# bipop_power_supply.net
KiCad netlist of a schematic drawn in EAGLE
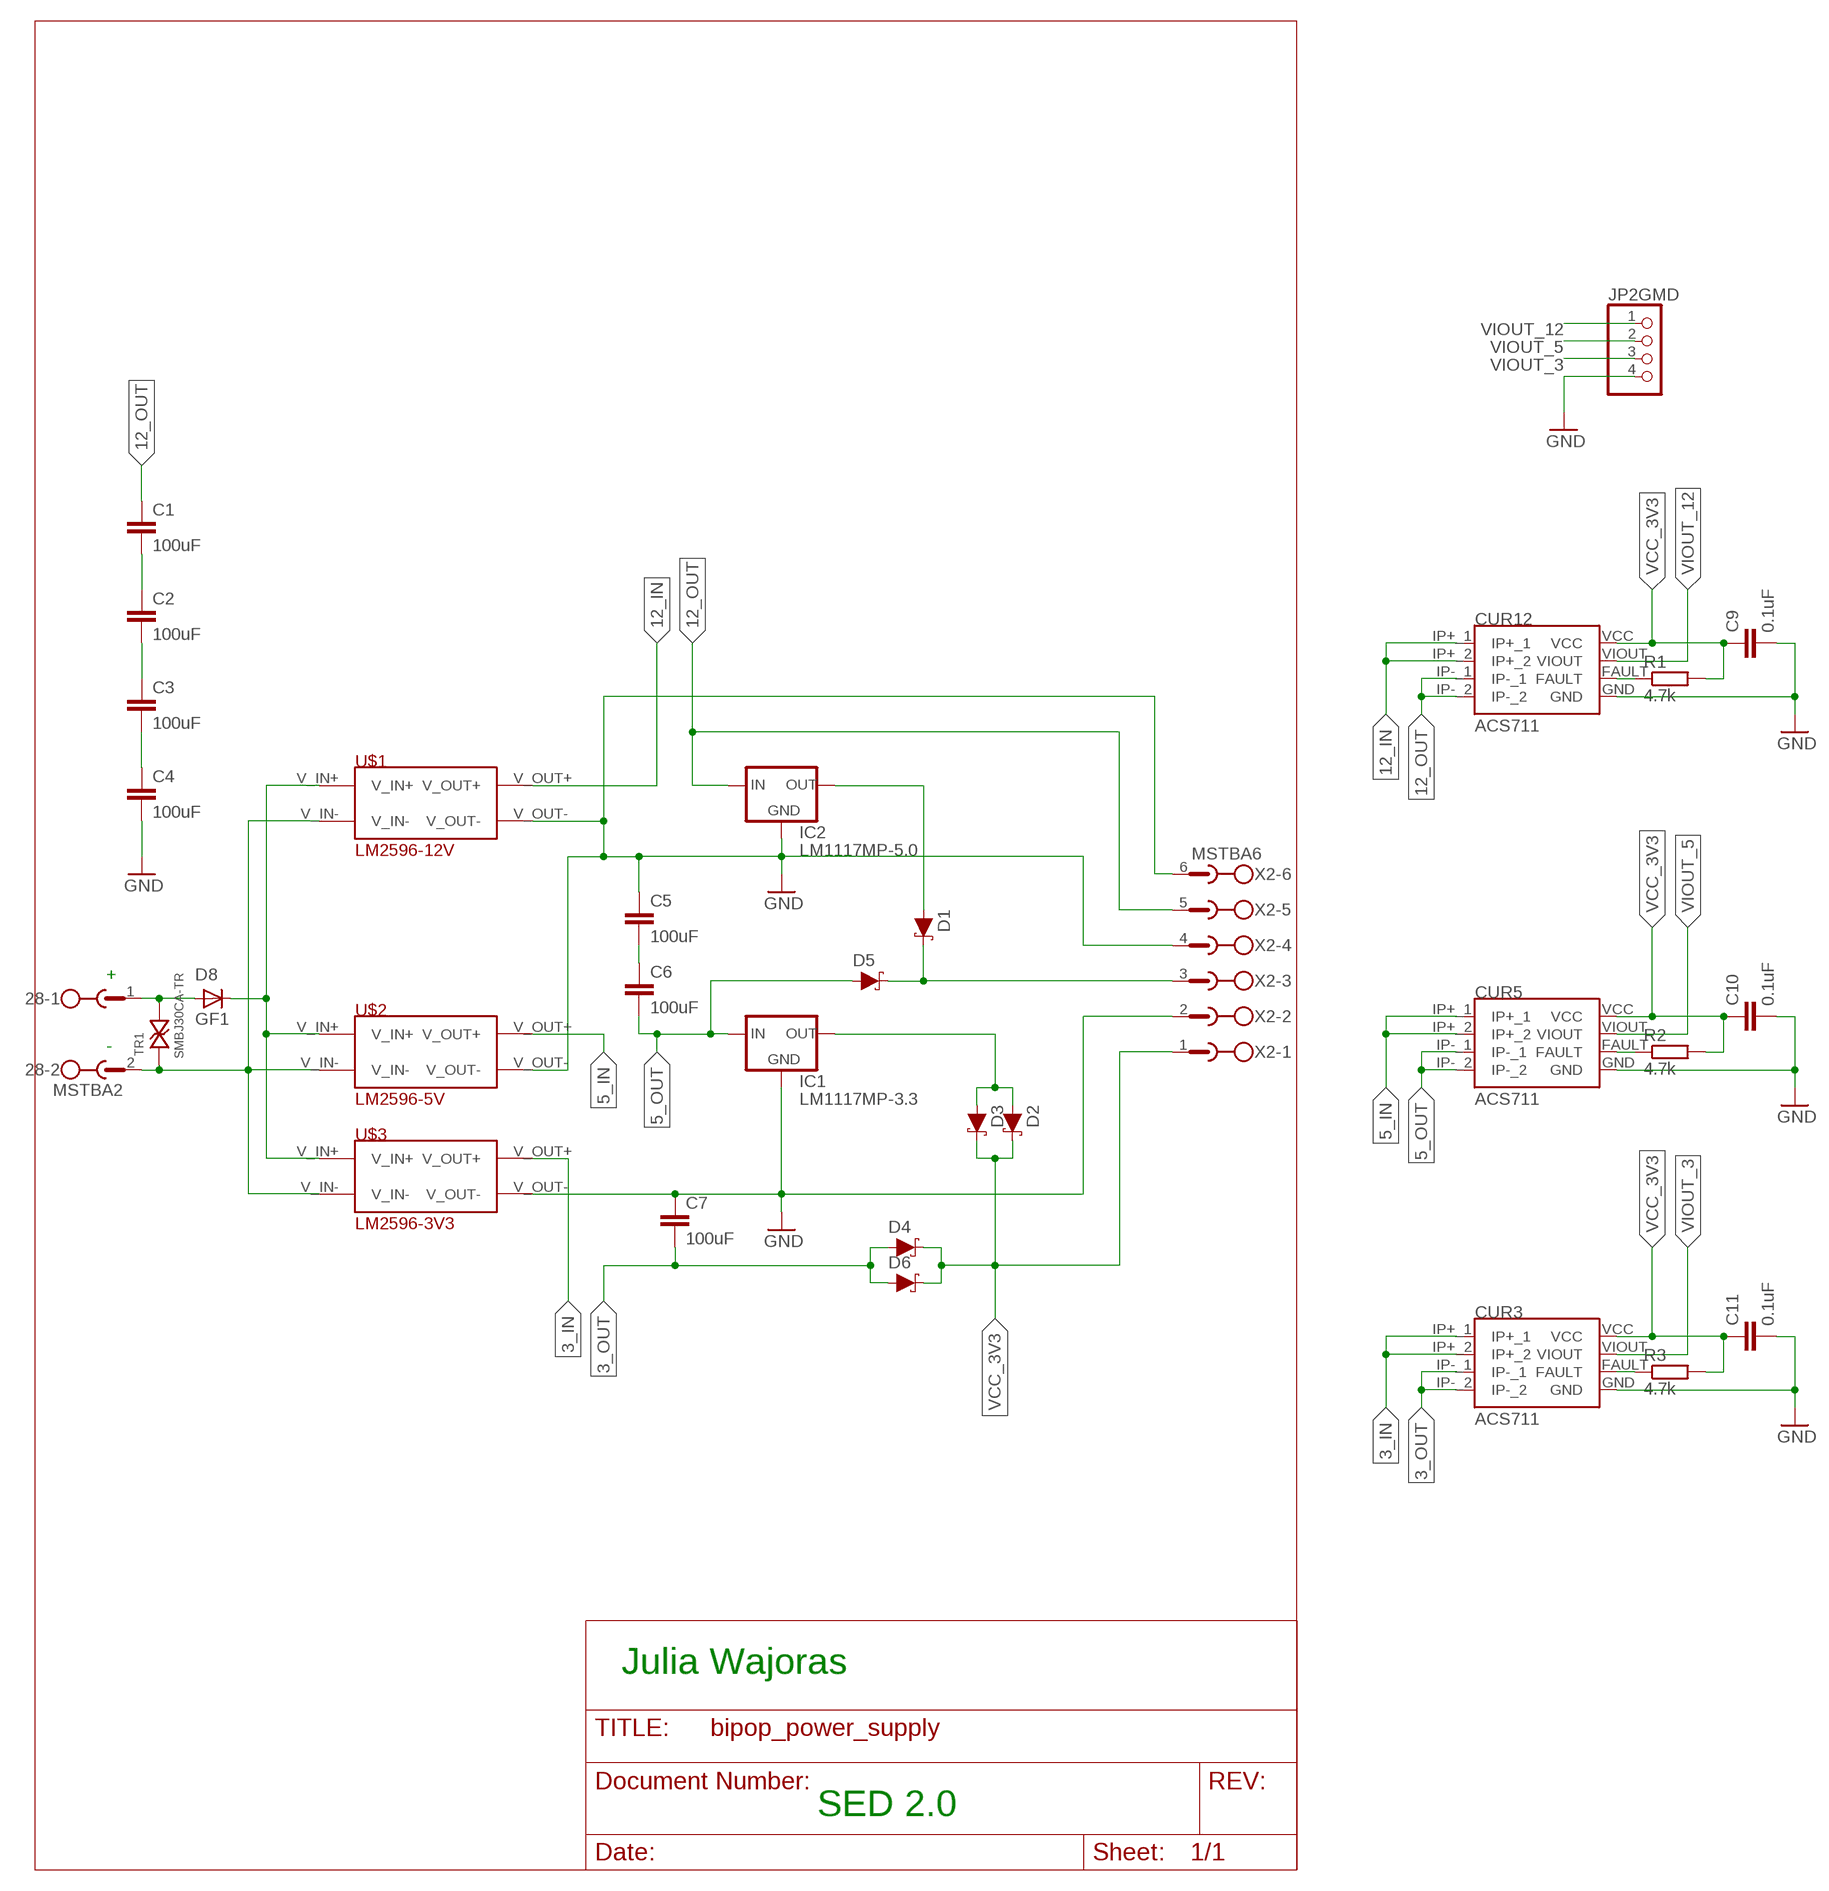
[diagram p0: schematic, sheet 1]

(export (version "E")
  (design (tool "Eeschema 10.0.6"))
  (components
    (comp (ref "28")
      (value "MSTBA2")
      (footprint "eagle-import:MSTBA2")
      (libsource (lib "eagle-import") (part "MSTBA2"))
    )
    (comp (ref "C1")
      (value "100uF")
      (footprint "eagle-import:C0805")
      (libsource (lib "eagle-import") (part "C-EUC0805"))
    )
    (comp (ref "C2")
      (value "100uF")
      (footprint "eagle-import:C0805")
      (libsource (lib "eagle-import") (part "C-EUC0805"))
    )
    (comp (ref "C3")
      (value "100uF")
      (footprint "eagle-import:C0805")
      (libsource (lib "eagle-import") (part "C-EUC0805"))
    )
    (comp (ref "C4")
      (value "100uF")
      (footprint "eagle-import:C0805")
      (libsource (lib "eagle-import") (part "C-EUC0805"))
    )
    (comp (ref "C5")
      (value "100uF")
      (footprint "eagle-import:C0805")
      (libsource (lib "eagle-import") (part "C-EUC0805"))
    )
    (comp (ref "C6")
      (value "100uF")
      (footprint "eagle-import:C0805")
      (libsource (lib "eagle-import") (part "C-EUC0805"))
    )
    (comp (ref "C7")
      (value "100uF")
      (footprint "eagle-import:C0805")
      (libsource (lib "eagle-import") (part "C-EUC0805"))
    )
    (comp (ref "C9")
      (value "0.1uF")
      (footprint "eagle-import:C0805")
      (libsource (lib "eagle-import") (part "C-EUC0805"))
    )
    (comp (ref "C10")
      (value "0.1uF")
      (footprint "eagle-import:C0805")
      (libsource (lib "eagle-import") (part "C-EUC0805"))
    )
    (comp (ref "C11")
      (value "0.1uF")
      (footprint "eagle-import:C0805")
      (libsource (lib "eagle-import") (part "C-EUC0805"))
    )
    (comp (ref "CUR3")
      (value "ACS711")
      (footprint "eagle-import:ACS711")
      (libsource (lib "eagle-import") (part "ACS711"))
    )
    (comp (ref "CUR5")
      (value "ACS711")
      (footprint "eagle-import:ACS711")
      (libsource (lib "eagle-import") (part "ACS711"))
    )
    (comp (ref "CUR12")
      (value "ACS711")
      (footprint "eagle-import:ACS711")
      (libsource (lib "eagle-import") (part "ACS711"))
    )
    (comp (ref "D1")
      (value "DIODE-SCHOTTKY-BAT20J")
      (footprint "eagle-import:SOD-323")
      (libsource (lib "eagle-import") (part "DIODE-SCHOTTKY-BAT20J"))
    )
    (comp (ref "D2")
      (value "DIODE-SCHOTTKY-BAT20J")
      (footprint "eagle-import:SOD-323")
      (libsource (lib "eagle-import") (part "DIODE-SCHOTTKY-BAT20J"))
    )
    (comp (ref "D3")
      (value "DIODE-SCHOTTKY-BAT20J")
      (footprint "eagle-import:SOD-323")
      (libsource (lib "eagle-import") (part "DIODE-SCHOTTKY-BAT20J"))
    )
    (comp (ref "D4")
      (value "DIODE-SCHOTTKY-BAT20J")
      (footprint "eagle-import:SOD-323")
      (libsource (lib "eagle-import") (part "DIODE-SCHOTTKY-BAT20J"))
    )
    (comp (ref "D5")
      (value "DIODE-SCHOTTKY-BAT20J")
      (footprint "eagle-import:SOD-323")
      (libsource (lib "eagle-import") (part "DIODE-SCHOTTKY-BAT20J"))
    )
    (comp (ref "D6")
      (value "DIODE-SCHOTTKY-BAT20J")
      (footprint "eagle-import:SOD-323")
      (libsource (lib "eagle-import") (part "DIODE-SCHOTTKY-BAT20J"))
    )
    (comp (ref "D8")
      (value "GF1")
      (footprint "eagle-import:SMA-DO214AC")
      (libsource (lib "eagle-import") (part "GF1"))
    )
    (comp (ref "IC1")
      (value "LM1117MP-3.3")
      (footprint "eagle-import:SOT223")
      (fields (field (name "MF") "Texas Instruments"))
      (libsource (lib "eagle-import") (part "LM1117?-MP3.3"))
    )
    (comp (ref "IC2")
      (value "LM1117MP-5.0")
      (footprint "eagle-import:SOT223")
      (fields (field (name "MF") "Texas Instruments"))
      (libsource (lib "eagle-import") (part "LM1117?-MP5.0"))
    )
    (comp (ref "JP2GMD")
      (value "PINHD-1X4")
      (footprint "eagle-import:1X04")
      (libsource (lib "eagle-import") (part "PINHD-1X4"))
    )
    (comp (ref "R1")
      (value "4.7k")
      (footprint "eagle-import:R0805")
      (libsource (lib "eagle-import") (part "R-EU_R0805"))
    )
    (comp (ref "R2")
      (value "4.7k")
      (footprint "eagle-import:R0805")
      (libsource (lib "eagle-import") (part "R-EU_R0805"))
    )
    (comp (ref "R3")
      (value "4.7k")
      (footprint "eagle-import:R0805")
      (libsource (lib "eagle-import") (part "R-EU_R0805"))
    )
    (comp (ref "TR1")
      (value "SMBJ30CA-TR")
      (footprint "eagle-import:DO214AC_BIDIR")
      (libsource (lib "eagle-import") (part "SMAJ30CA-TR__DO214AC"))
    )
    (comp (ref "U$1")
      (value "LM2596-12V")
      (footprint "eagle-import:DC-DC_CONVERTER")
      (libsource (lib "eagle-import") (part "LM2596-12V"))
    )
    (comp (ref "U$2")
      (value "LM2596-5V")
      (footprint "eagle-import:DC-DC_CONVERTER")
      (libsource (lib "eagle-import") (part "LM2596-5V"))
    )
    (comp (ref "U$3")
      (value "LM2596-3V3")
      (footprint "eagle-import:DC-DC_CONVERTER")
      (libsource (lib "eagle-import") (part "LM2596-3V3"))
    )
    (comp (ref "X2")
      (value "MSTBA6")
      (footprint "eagle-import:MSTBA6")
      (fields (field (name "MF") "FARNELL") (field (name "MPN") "1757284"))
      (libsource (lib "eagle-import") (part "MSTBA6"))
    )
  )
  (nets
    (net (code "1") (name "3_IN") (class "Default")
      (node (ref "CUR3") (pin "IP+_1") (pinfunction "IP+_1_IP+_1") (pintype "bidirectional"))
      (node (ref "CUR3") (pin "IP+_2") (pinfunction "IP+_2_IP+_2") (pintype "bidirectional"))
      (node (ref "U$3") (pin "V_OUT+") (pinfunction "V_OUT+_V_OUT+") (pintype "bidirectional"))
    )
    (net (code "2") (name "3_OUT") (class "Default")
      (node (ref "C7") (pin "2") (pinfunction "2_2") (pintype "passive"))
      (node (ref "CUR3") (pin "IP-_1") (pinfunction "IP-_1_IP-_1") (pintype "bidirectional"))
      (node (ref "CUR3") (pin "IP-_2") (pinfunction "IP-_2_IP-_2") (pintype "bidirectional"))
      (node (ref "D4") (pin "A") (pinfunction "A_A") (pintype "passive"))
      (node (ref "D6") (pin "A") (pinfunction "A_A") (pintype "passive"))
    )
    (net (code "3") (name "5_IN") (class "Default")
      (node (ref "CUR5") (pin "IP+_1") (pinfunction "IP+_1_IP+_1") (pintype "bidirectional"))
      (node (ref "CUR5") (pin "IP+_2") (pinfunction "IP+_2_IP+_2") (pintype "bidirectional"))
      (node (ref "U$2") (pin "V_OUT+") (pinfunction "V_OUT+_V_OUT+") (pintype "bidirectional"))
    )
    (net (code "4") (name "5_OUT") (class "Default")
      (node (ref "C6") (pin "2") (pinfunction "2_2") (pintype "passive"))
      (node (ref "CUR5") (pin "IP-_1") (pinfunction "IP-_1_IP-_1") (pintype "bidirectional"))
      (node (ref "CUR5") (pin "IP-_2") (pinfunction "IP-_2_IP-_2") (pintype "bidirectional"))
      (node (ref "D5") (pin "A") (pinfunction "A_A") (pintype "passive"))
      (node (ref "IC1") (pin "3") (pinfunction "IN_3") (pintype "input"))
    )
    (net (code "5") (name "12_IN") (class "Default")
      (node (ref "CUR12") (pin "IP+_1") (pinfunction "IP+_1_IP+_1") (pintype "bidirectional"))
      (node (ref "CUR12") (pin "IP+_2") (pinfunction "IP+_2_IP+_2") (pintype "bidirectional"))
      (node (ref "U$1") (pin "V_OUT+") (pinfunction "V_OUT+_V_OUT+") (pintype "bidirectional"))
    )
    (net (code "6") (name "12_OUT") (class "Default")
      (node (ref "C1") (pin "1") (pinfunction "1_1") (pintype "passive"))
      (node (ref "CUR12") (pin "IP-_1") (pinfunction "IP-_1_IP-_1") (pintype "bidirectional"))
      (node (ref "CUR12") (pin "IP-_2") (pinfunction "IP-_2_IP-_2") (pintype "bidirectional"))
      (node (ref "IC2") (pin "3") (pinfunction "IN_3") (pintype "input"))
      (node (ref "X2") (pin "5") (pinfunction "1_5") (pintype "passive"))
    )
    (net (code "7") (name "GND") (class "Default")
      (node (ref "C10") (pin "2") (pinfunction "2_2") (pintype "passive"))
      (node (ref "C11") (pin "2") (pinfunction "2_2") (pintype "passive"))
      (node (ref "C4") (pin "2") (pinfunction "2_2") (pintype "passive"))
      (node (ref "C5") (pin "1") (pinfunction "1_1") (pintype "passive"))
      (node (ref "C7") (pin "1") (pinfunction "1_1") (pintype "passive"))
      (node (ref "C9") (pin "2") (pinfunction "2_2") (pintype "passive"))
      (node (ref "CUR12") (pin "GND") (pinfunction "GND_GND") (pintype "bidirectional"))
      (node (ref "CUR3") (pin "GND") (pinfunction "GND_GND") (pintype "bidirectional"))
      (node (ref "CUR5") (pin "GND") (pinfunction "GND_GND") (pintype "bidirectional"))
      (node (ref "IC1") (pin "1") (pinfunction "GND_1") (pintype "input"))
      (node (ref "IC2") (pin "1") (pinfunction "GND_1") (pintype "input"))
      (node (ref "JP2GMD") (pin "4") (pinfunction "4_4") (pintype "passive"))
      (node (ref "U$1") (pin "V_OUT-") (pinfunction "V_OUT-_V_OUT-") (pintype "bidirectional"))
      (node (ref "U$2") (pin "V_OUT-") (pinfunction "V_OUT-_V_OUT-") (pintype "bidirectional"))
      (node (ref "U$3") (pin "V_OUT-") (pinfunction "V_OUT-_V_OUT-") (pintype "bidirectional"))
      (node (ref "X2") (pin "2") (pinfunction "1_2") (pintype "passive"))
      (node (ref "X2") (pin "4") (pinfunction "1_4") (pintype "passive"))
      (node (ref "X2") (pin "6") (pinfunction "1_6") (pintype "passive"))
    )
    (net (code "8") (name "Net-(28-Pad1)") (class "Default")
      (node (ref "28") (pin "1") (pinfunction "1_1") (pintype "passive"))
      (node (ref "D8") (pin "A") (pinfunction "A_A") (pintype "passive"))
      (node (ref "TR1") (pin "P$2") (pinfunction "P$2_P$2") (pintype "passive"))
    )
    (net (code "9") (name "Net-(28B-1)") (class "Default")
      (node (ref "28") (pin "2") (pinfunction "1_2") (pintype "passive"))
      (node (ref "TR1") (pin "P$1") (pinfunction "P$1_P$1") (pintype "passive"))
      (node (ref "U$1") (pin "V_IN-") (pinfunction "V_IN-_V_IN-") (pintype "bidirectional"))
      (node (ref "U$2") (pin "V_IN-") (pinfunction "V_IN-_V_IN-") (pintype "bidirectional"))
      (node (ref "U$3") (pin "V_IN-") (pinfunction "V_IN-_V_IN-") (pintype "bidirectional"))
    )
    (net (code "10") (name "Net-(C1-Pad2)") (class "Default")
      (node (ref "C1") (pin "2") (pinfunction "2_2") (pintype "passive"))
      (node (ref "C2") (pin "1") (pinfunction "1_1") (pintype "passive"))
    )
    (net (code "11") (name "Net-(C2-Pad2)") (class "Default")
      (node (ref "C2") (pin "2") (pinfunction "2_2") (pintype "passive"))
      (node (ref "C3") (pin "1") (pinfunction "1_1") (pintype "passive"))
    )
    (net (code "12") (name "Net-(C3-Pad2)") (class "Default")
      (node (ref "C3") (pin "2") (pinfunction "2_2") (pintype "passive"))
      (node (ref "C4") (pin "1") (pinfunction "1_1") (pintype "passive"))
    )
    (net (code "13") (name "Net-(C5-Pad2)") (class "Default")
      (node (ref "C5") (pin "2") (pinfunction "2_2") (pintype "passive"))
      (node (ref "C6") (pin "1") (pinfunction "1_1") (pintype "passive"))
    )
    (net (code "14") (name "Net-(CUR3-PadFAULT)") (class "Default")
      (node (ref "CUR3") (pin "FAULT") (pinfunction "FAULT_FAULT") (pintype "bidirectional"))
      (node (ref "R3") (pin "1") (pinfunction "1_1") (pintype "passive"))
    )
    (net (code "15") (name "Net-(CUR5-PadFAULT)") (class "Default")
      (node (ref "CUR5") (pin "FAULT") (pinfunction "FAULT_FAULT") (pintype "bidirectional"))
      (node (ref "R2") (pin "1") (pinfunction "1_1") (pintype "passive"))
    )
    (net (code "16") (name "Net-(CUR12-PadFAULT)") (class "Default")
      (node (ref "CUR12") (pin "FAULT") (pinfunction "FAULT_FAULT") (pintype "bidirectional"))
      (node (ref "R1") (pin "1") (pinfunction "1_1") (pintype "passive"))
    )
    (net (code "17") (name "Net-(D8-C)") (class "Default")
      (node (ref "D8") (pin "K") (pinfunction "C_K") (pintype "passive"))
      (node (ref "U$1") (pin "V_IN+") (pinfunction "V_IN+_V_IN+") (pintype "bidirectional"))
      (node (ref "U$2") (pin "V_IN+") (pinfunction "V_IN+_V_IN+") (pintype "bidirectional"))
      (node (ref "U$3") (pin "V_IN+") (pinfunction "V_IN+_V_IN+") (pintype "bidirectional"))
    )
    (net (code "18") (name "Net-(IC1-OUT)") (class "Default")
      (node (ref "D2") (pin "A") (pinfunction "A_A") (pintype "passive"))
      (node (ref "D3") (pin "A") (pinfunction "A_A") (pintype "passive"))
      (node (ref "IC1") (pin "2") (pinfunction "OUT_2") (pintype "passive"))
    )
    (net (code "19") (name "Net-(IC2-OUT)") (class "Default")
      (node (ref "D1") (pin "A") (pinfunction "A_A") (pintype "passive"))
      (node (ref "IC2") (pin "2") (pinfunction "OUT_2") (pintype "passive"))
    )
    (net (code "20") (name "Net-(X2C-1)") (class "Default")
      (node (ref "D1") (pin "C") (pinfunction "C_C") (pintype "passive"))
      (node (ref "D5") (pin "C") (pinfunction "C_C") (pintype "passive"))
      (node (ref "X2") (pin "3") (pinfunction "1_3") (pintype "passive"))
    )
    (net (code "21") (name "VCC_3V3") (class "Default")
      (node (ref "C10") (pin "1") (pinfunction "1_1") (pintype "passive"))
      (node (ref "C11") (pin "1") (pinfunction "1_1") (pintype "passive"))
      (node (ref "C9") (pin "1") (pinfunction "1_1") (pintype "passive"))
      (node (ref "CUR12") (pin "VCC") (pinfunction "VCC_VCC") (pintype "bidirectional"))
      (node (ref "CUR3") (pin "VCC") (pinfunction "VCC_VCC") (pintype "bidirectional"))
      (node (ref "CUR5") (pin "VCC") (pinfunction "VCC_VCC") (pintype "bidirectional"))
      (node (ref "D2") (pin "C") (pinfunction "C_C") (pintype "passive"))
      (node (ref "D3") (pin "C") (pinfunction "C_C") (pintype "passive"))
      (node (ref "D4") (pin "C") (pinfunction "C_C") (pintype "passive"))
      (node (ref "D6") (pin "C") (pinfunction "C_C") (pintype "passive"))
      (node (ref "R1") (pin "2") (pinfunction "2_2") (pintype "passive"))
      (node (ref "R2") (pin "2") (pinfunction "2_2") (pintype "passive"))
      (node (ref "R3") (pin "2") (pinfunction "2_2") (pintype "passive"))
      (node (ref "X2") (pin "1") (pinfunction "1_1") (pintype "passive"))
    )
    (net (code "22") (name "VIOUT_3") (class "Default")
      (node (ref "CUR3") (pin "VIOUT") (pinfunction "VIOUT_VIOUT") (pintype "bidirectional"))
      (node (ref "JP2GMD") (pin "3") (pinfunction "3_3") (pintype "passive"))
    )
    (net (code "23") (name "VIOUT_5") (class "Default")
      (node (ref "CUR5") (pin "VIOUT") (pinfunction "VIOUT_VIOUT") (pintype "bidirectional"))
      (node (ref "JP2GMD") (pin "2") (pinfunction "2_2") (pintype "passive"))
    )
    (net (code "24") (name "VIOUT_12") (class "Default")
      (node (ref "CUR12") (pin "VIOUT") (pinfunction "VIOUT_VIOUT") (pintype "bidirectional"))
      (node (ref "JP2GMD") (pin "1") (pinfunction "1_1") (pintype "passive"))
    )
  )
)
